# SC8701_EVM_RE1_0620.net
KiCad netlist of a schematic drawn in Altium Designer
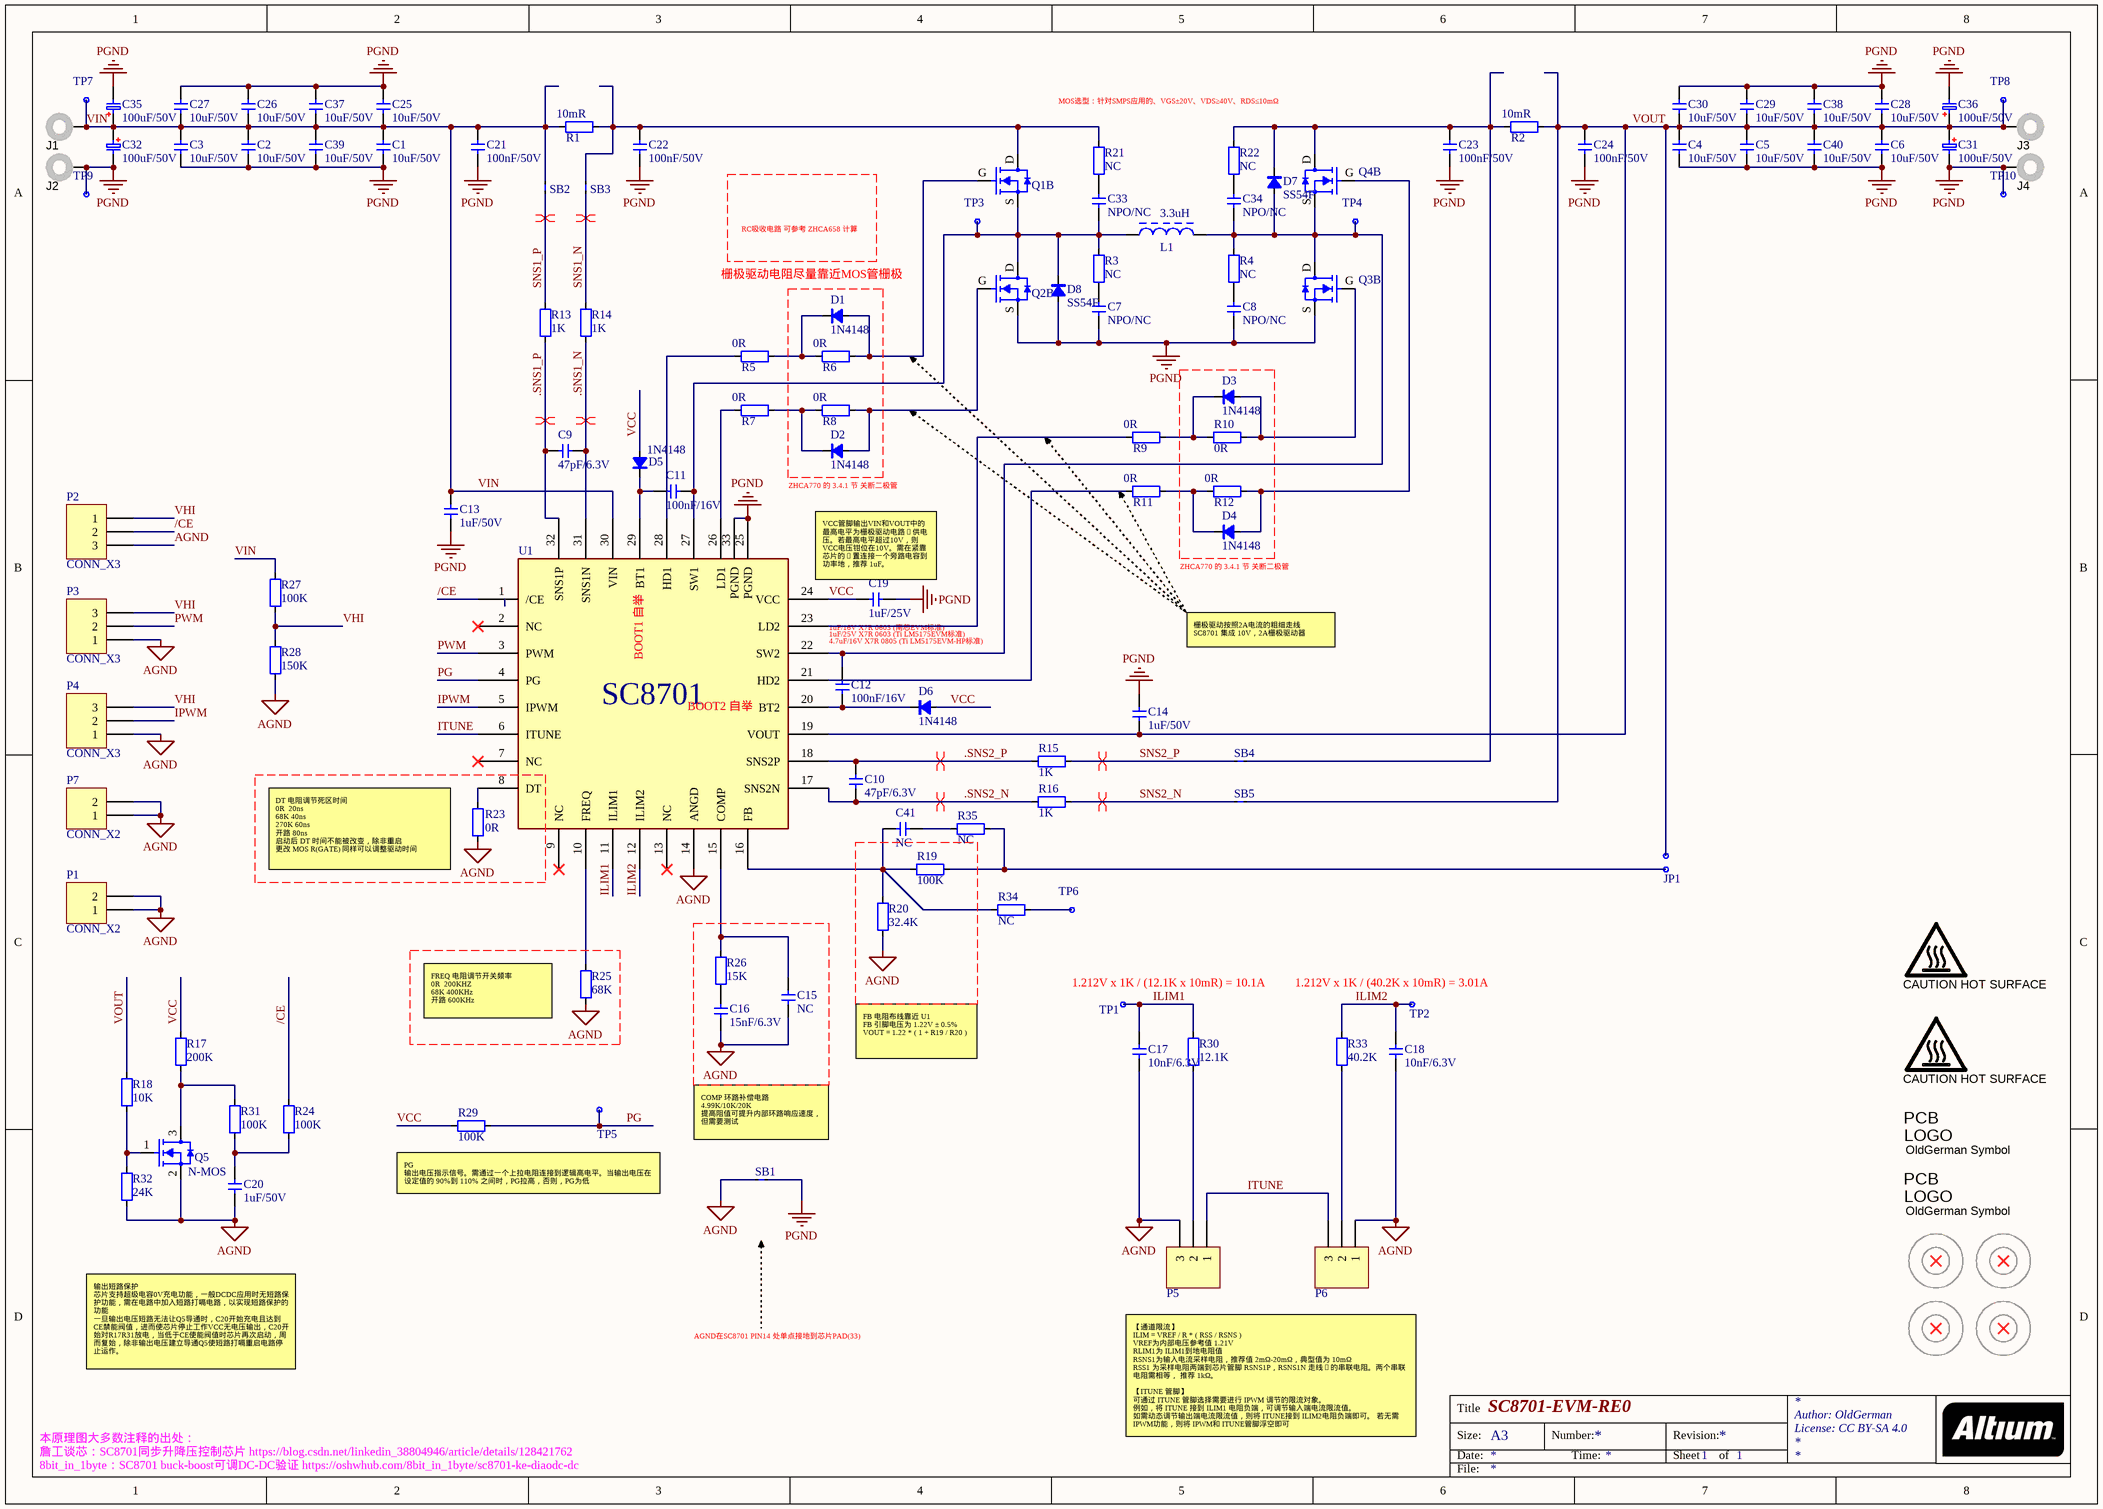
[diagram p0: SC8701_EVM_RE1_0620.SchDoc]

(export (version "E")
  (design (tool "Eeschema 10.0.6"))
  (components
    (comp (ref "C1")
      (value "10uF/50V")
      (footprint "C1210")
      (description "Capacitor")
      (libsource (lib "ODG_AD_Lib") (part "CAP"))
    )
    (comp (ref "C2")
      (value "10uF/50V")
      (footprint "C1210")
      (description "Capacitor")
      (libsource (lib "ODG_AD_Lib") (part "CAP"))
    )
    (comp (ref "C3")
      (value "10uF/50V")
      (footprint "C1210")
      (description "Capacitor")
      (libsource (lib "ODG_AD_Lib") (part "CAP"))
    )
    (comp (ref "C4")
      (value "10uF/50V")
      (footprint "C1210")
      (description "Capacitor")
      (libsource (lib "ODG_AD_Lib") (part "CAP"))
    )
    (comp (ref "C5")
      (value "10uF/50V")
      (footprint "C1210")
      (description "Capacitor")
      (libsource (lib "ODG_AD_Lib") (part "CAP"))
    )
    (comp (ref "C6")
      (value "10uF/50V")
      (footprint "C1210")
      (description "Capacitor")
      (libsource (lib "ODG_AD_Lib") (part "CAP"))
    )
    (comp (ref "C7")
      (value "NPO/NC")
      (footprint "C0805")
      (description "Capacitor")
      (libsource (lib "ODG_AD_Lib") (part "CAP"))
    )
    (comp (ref "C8")
      (value "NPO/NC")
      (footprint "C0805")
      (description "Capacitor")
      (libsource (lib "ODG_AD_Lib") (part "CAP"))
    )
    (comp (ref "C9")
      (value "47pF/6.3V")
      (footprint "C0603")
      (description "Capacitor")
      (libsource (lib "ODG_AD_Lib") (part "CAP"))
    )
    (comp (ref "C10")
      (value "47pF/6.3V")
      (footprint "C0603")
      (description "Capacitor")
      (libsource (lib "ODG_AD_Lib") (part "CAP"))
    )
    (comp (ref "C11")
      (value "100nF/16V")
      (footprint "C0603")
      (description "Capacitor")
      (libsource (lib "ODG_AD_Lib") (part "CAP"))
    )
    (comp (ref "C12")
      (value "100nF/16V")
      (footprint "C0603")
      (description "Capacitor")
      (libsource (lib "ODG_AD_Lib") (part "CAP"))
    )
    (comp (ref "C13")
      (value "1uF/50V")
      (footprint "C0603")
      (description "Capacitor")
      (libsource (lib "ODG_AD_Lib") (part "CAP"))
    )
    (comp (ref "C14")
      (value "1uF/50V")
      (footprint "C0603")
      (description "Capacitor")
      (libsource (lib "ODG_AD_Lib") (part "CAP"))
    )
    (comp (ref "C15")
      (value "NC")
      (footprint "C0603")
      (description "Capacitor")
      (libsource (lib "ODG_AD_Lib") (part "CAP"))
    )
    (comp (ref "C16")
      (value "15nF/6.3V")
      (footprint "C0603")
      (description "Capacitor")
      (libsource (lib "ODG_AD_Lib") (part "CAP"))
    )
    (comp (ref "C17")
      (value "10nF/6.3V")
      (footprint "C0603")
      (description "Capacitor")
      (libsource (lib "ODG_AD_Lib") (part "CAP"))
    )
    (comp (ref "C18")
      (value "10nF/6.3V")
      (footprint "C0603")
      (description "Capacitor")
      (libsource (lib "ODG_AD_Lib") (part "CAP"))
    )
    (comp (ref "C19")
      (value "1uF/25V")
      (footprint "C0805")
      (description "Capacitor")
      (libsource (lib "ODG_AD_Lib") (part "CAP"))
    )
    (comp (ref "C20")
      (value "1uF/50V")
      (footprint "C0603")
      (description "Capacitor")
      (libsource (lib "ODG_AD_Lib") (part "CAP"))
    )
    (comp (ref "C21")
      (value "100nF/50V")
      (footprint "C0603")
      (description "Capacitor")
      (libsource (lib "ODG_AD_Lib") (part "CAP"))
    )
    (comp (ref "C22")
      (value "100nF/50V")
      (footprint "C0603")
      (description "Capacitor")
      (libsource (lib "ODG_AD_Lib") (part "CAP"))
    )
    (comp (ref "C23")
      (value "100nF/50V")
      (footprint "C0603")
      (description "Capacitor")
      (libsource (lib "ODG_AD_Lib") (part "CAP"))
    )
    (comp (ref "C24")
      (value "100nF/50V")
      (footprint "C0603")
      (description "Capacitor")
      (libsource (lib "ODG_AD_Lib") (part "CAP"))
    )
    (comp (ref "C25")
      (value "10uF/50V")
      (footprint "C1210")
      (description "Capacitor")
      (libsource (lib "ODG_AD_Lib") (part "CAP"))
    )
    (comp (ref "C26")
      (value "10uF/50V")
      (footprint "C1210")
      (description "Capacitor")
      (libsource (lib "ODG_AD_Lib") (part "CAP"))
    )
    (comp (ref "C27")
      (value "10uF/50V")
      (footprint "C1210")
      (description "Capacitor")
      (libsource (lib "ODG_AD_Lib") (part "CAP"))
    )
    (comp (ref "C28")
      (value "10uF/50V")
      (footprint "C1210")
      (description "Capacitor")
      (libsource (lib "ODG_AD_Lib") (part "CAP"))
    )
    (comp (ref "C29")
      (value "10uF/50V")
      (footprint "C1210")
      (description "Capacitor")
      (libsource (lib "ODG_AD_Lib") (part "CAP"))
    )
    (comp (ref "C30")
      (value "10uF/50V")
      (footprint "C1210")
      (description "Capacitor")
      (libsource (lib "ODG_AD_Lib") (part "CAP"))
    )
    (comp (ref "C31")
      (value "100uF/50V")
      (footprint "CAP OS-CON D=10.0 L=10.0 F10")
      (description "Capacitor")
      (libsource (lib "ODG_AD_Lib") (part "CAP_Polar_Aluminum"))
    )
    (comp (ref "C32")
      (value "100uF/50V")
      (footprint "CAP OS-CON D=10.0 L=10.0 F10")
      (description "Capacitor")
      (libsource (lib "ODG_AD_Lib") (part "CAP_Polar_Aluminum"))
    )
    (comp (ref "C33")
      (value "NPO/NC")
      (footprint "C0805")
      (description "Capacitor")
      (libsource (lib "ODG_AD_Lib") (part "CAP"))
    )
    (comp (ref "C34")
      (value "NPO/NC")
      (footprint "C0805")
      (description "Capacitor")
      (libsource (lib "ODG_AD_Lib") (part "CAP"))
    )
    (comp (ref "C35")
      (value "100uF/50V")
      (footprint "CAP OS-CON D=10.0 L=10.0 F10")
      (description "Capacitor")
      (libsource (lib "ODG_AD_Lib") (part "CAP_Polar_Aluminum"))
    )
    (comp (ref "C36")
      (value "100uF/50V")
      (footprint "CAP OS-CON D=10.0 L=10.0 F10")
      (description "Capacitor")
      (libsource (lib "ODG_AD_Lib") (part "CAP_Polar_Aluminum"))
    )
    (comp (ref "C37")
      (value "10uF/50V")
      (footprint "C1210")
      (description "Capacitor")
      (libsource (lib "ODG_AD_Lib") (part "CAP"))
    )
    (comp (ref "C38")
      (value "10uF/50V")
      (footprint "C1210")
      (description "Capacitor")
      (libsource (lib "ODG_AD_Lib") (part "CAP"))
    )
    (comp (ref "C39")
      (value "10uF/50V")
      (footprint "C1210")
      (description "Capacitor")
      (libsource (lib "ODG_AD_Lib") (part "CAP"))
    )
    (comp (ref "C40")
      (value "10uF/50V")
      (footprint "C1210")
      (description "Capacitor")
      (libsource (lib "ODG_AD_Lib") (part "CAP"))
    )
    (comp (ref "C41")
      (value "NC")
      (footprint "C0603")
      (description "Capacitor")
      (libsource (lib "ODG_AD_Lib") (part "CAP"))
    )
    (comp (ref "D1")
      (value "1N4148")
      (footprint "SOD-323")
      (description "二极管")
      (libsource (lib "ODG_AD_Lib") (part "DIODE"))
    )
    (comp (ref "D2")
      (value "1N4148")
      (footprint "SOD-323")
      (description "二极管")
      (libsource (lib "ODG_AD_Lib") (part "DIODE"))
    )
    (comp (ref "D3")
      (value "1N4148")
      (footprint "SOD-323")
      (description "二极管")
      (libsource (lib "ODG_AD_Lib") (part "DIODE"))
    )
    (comp (ref "D4")
      (value "1N4148")
      (footprint "SOD-323")
      (description "二极管")
      (libsource (lib "ODG_AD_Lib") (part "DIODE"))
    )
    (comp (ref "D5")
      (value "1N4148")
      (footprint "SOD-323")
      (description "二极管")
      (libsource (lib "") (part "DIODE_2"))
    )
    (comp (ref "D6")
      (value "1N4148")
      (footprint "SOD-323")
      (description "二极管")
      (libsource (lib "ODG_AD_Lib") (part "DIODE"))
    )
    (comp (ref "D7")
      (value "SS54F")
      (footprint "SMAF")
      (description "二极管")
      (libsource (lib "") (part "DIODE_1"))
    )
    (comp (ref "D8")
      (value "SS54F")
      (footprint "SMAF")
      (description "二极管")
      (libsource (lib "") (part "DIODE_1"))
    )
    (comp (ref "H1") (value "HOLE") (footprint "M3.2 D=8") (libsource (lib "ODG_AD_Lib") (part "HOLE")))
    (comp (ref "H2") (value "HOLE") (footprint "M3.2 D=8") (libsource (lib "ODG_AD_Lib") (part "HOLE")))
    (comp (ref "H3") (value "HOLE") (footprint "M3.2 D=8") (libsource (lib "ODG_AD_Lib") (part "HOLE")))
    (comp (ref "H4") (value "HOLE") (footprint "M3.2 D=8") (libsource (lib "ODG_AD_Lib") (part "HOLE")))
    (comp (ref "J1")
      (value "U6047")
      (footprint "JACK_BANANA_U6047")
      (description "Banana Jack")
      (fields
        (field (name "PARTNUMBER") "575-8")
        (field (name "MANUFACTURER") "Keystone")
        (field (name "PUBLISHER") "Texas Instruments")
      )
      (libsource (lib "ODG_AD_Lib") (part "JACK_BANANA"))
    )
    (comp (ref "J2")
      (value "U6047")
      (footprint "JACK_BANANA_U6047")
      (description "Banana Jack")
      (fields
        (field (name "PARTNUMBER") "575-8")
        (field (name "MANUFACTURER") "Keystone")
        (field (name "PUBLISHER") "Texas Instruments")
      )
      (libsource (lib "ODG_AD_Lib") (part "JACK_BANANA"))
    )
    (comp (ref "J3")
      (value "U6047")
      (footprint "JACK_BANANA_U6047")
      (description "Banana Jack")
      (fields
        (field (name "PARTNUMBER") "575-8")
        (field (name "MANUFACTURER") "Keystone")
        (field (name "PUBLISHER") "Texas Instruments")
      )
      (libsource (lib "ODG_AD_Lib") (part "JACK_BANANA"))
    )
    (comp (ref "J4")
      (value "U6047")
      (footprint "JACK_BANANA_U6047")
      (description "Banana Jack")
      (fields
        (field (name "PARTNUMBER") "575-8")
        (field (name "MANUFACTURER") "Keystone")
        (field (name "PUBLISHER") "Texas Instruments")
      )
      (libsource (lib "ODG_AD_Lib") (part "JACK_BANANA"))
    )
    (comp (ref "JP1")
      (value "CONN_X2_DOT")
      (footprint "2.54mm_Male_x2")
      (libsource (lib "ODG_AD_Lib") (part "CONN_X2_DOT"))
    )
    (comp (ref "L1")
      (value "3.3uH")
      (footprint "INDUCTOR 1350 12.6X13.5X5.0mm")
      (description "135 功率电感 额定电流15A")
      (libsource (lib "ODG_AD_Lib") (part "Inductor_power"))
    )
    (comp (ref "LOGO1")
      (value "CAUTION HOT SURFACE")
      (footprint "IEC_HotSurface_Small")
      (description "IEC 61010-1 Hot Surface Warning")
      (fields (field (name "SYMBOLCREATOR") "a0412235") (field (name "PUBLISHER") "Texas Instruments"))
      (libsource (lib "ODG_AD_Lib") (part "IEC_HotSurface"))
    )
    (comp (ref "LOGO2")
      (value "CAUTION HOT SURFACE")
      (footprint "IEC_HotSurface_Small")
      (description "IEC 61010-1 Hot Surface Warning")
      (fields (field (name "SYMBOLCREATOR") "a0412235") (field (name "PUBLISHER") "Texas Instruments"))
      (libsource (lib "ODG_AD_Lib") (part "IEC_HotSurface"))
    )
    (comp (ref "Logo3")
      (value "OldGerman Symbol")
      (footprint "ODG_LOGO")
      (fields (field (name "SYMBOLCREATOR") "a0412235") (field (name "PUBLISHER") "Texas Instruments"))
      (libsource (lib "ODG_AD_Lib") (part "OldGeman"))
    )
    (comp (ref "Logo4")
      (value "OldGerman Symbol")
      (footprint "ODG_LOGO")
      (fields (field (name "SYMBOLCREATOR") "a0412235") (field (name "PUBLISHER") "Texas Instruments"))
      (libsource (lib "ODG_AD_Lib") (part "OldGeman"))
    )
    (comp (ref "P1")
      (value "CONN_X2")
      (footprint "2.54mm_Male_x2")
      (libsource (lib "ODG_AD_Lib") (part "CONN_X2"))
    )
    (comp (ref "P2") (value "CONN_X3") (footprint "2.54mm_Male_x3") (libsource (lib "") (part "CONN_X3_1")))
    (comp (ref "P3")
      (value "CONN_X3")
      (footprint "2.54mm_Male_x3")
      (libsource (lib "ODG_AD_Lib") (part "CONN_X3"))
    )
    (comp (ref "P4")
      (value "CONN_X3")
      (footprint "2.54mm_Male_x3")
      (libsource (lib "ODG_AD_Lib") (part "CONN_X3"))
    )
    (comp (ref "P5") (value "CONN_X3") (footprint "2.54mm_Male_x3") (libsource (lib "") (part "CONN_X3_1")))
    (comp (ref "P6") (value "CONN_X3") (footprint "2.54mm_Male_x3") (libsource (lib "") (part "CONN_X3_1")))
    (comp (ref "P7")
      (value "CONN_X2")
      (footprint "2.54mm_Male_x2")
      (libsource (lib "ODG_AD_Lib") (part "CONN_X2"))
    )
    (comp (ref "Q1B")
      (value "N-MOS_GDS")
      (footprint "SO8FL ROUND")
      (libsource (lib "ODG_AD_Lib") (part "N-MOS_GDS"))
    )
    (comp (ref "Q2B")
      (value "N-MOS_GDS")
      (footprint "SO8FL ROUND")
      (libsource (lib "ODG_AD_Lib") (part "N-MOS_GDS"))
    )
    (comp (ref "Q3B")
      (value "N-MOS_GDS")
      (footprint "SO8FL ROUND")
      (libsource (lib "ODG_AD_Lib") (part "N-MOS_GDS"))
    )
    (comp (ref "Q4B")
      (value "N-MOS_GDS")
      (footprint "SO8FL ROUND")
      (libsource (lib "ODG_AD_Lib") (part "N-MOS_GDS"))
    )
    (comp (ref "Q5")
      (value "N-MOS")
      (footprint "INFINEON SOT-23-3")
      (libsource (lib "ODG_AD_Lib") (part "N-MOS_123"))
    )
    (comp (ref "R1")
      (value "10mR")
      (footprint "R1206")
      (description "IEC Standard")
      (libsource (lib "") (part "RES_2"))
    )
    (comp (ref "R2")
      (value "10mR")
      (footprint "R1206")
      (description "IEC Standard")
      (libsource (lib "") (part "RES_2"))
    )
    (comp (ref "R3")
      (value "NC")
      (footprint "R0805")
      (description "IEC Standard")
      (libsource (lib "ODG_AD_Lib") (part "RES"))
    )
    (comp (ref "R4")
      (value "NC")
      (footprint "R0805")
      (description "IEC Standard")
      (libsource (lib "ODG_AD_Lib") (part "RES"))
    )
    (comp (ref "R5")
      (value "0R")
      (footprint "R0603")
      (description "IEC Standard")
      (libsource (lib "") (part "RES_2"))
    )
    (comp (ref "R6")
      (value "0R")
      (footprint "R0603")
      (description "IEC Standard")
      (libsource (lib "") (part "RES_2"))
    )
    (comp (ref "R7")
      (value "0R")
      (footprint "R0603")
      (description "IEC Standard")
      (libsource (lib "") (part "RES_2"))
    )
    (comp (ref "R8")
      (value "0R")
      (footprint "R0603")
      (description "IEC Standard")
      (libsource (lib "") (part "RES_2"))
    )
    (comp (ref "R9")
      (value "0R")
      (footprint "R0603")
      (description "IEC Standard")
      (libsource (lib "") (part "RES_2"))
    )
    (comp (ref "R10")
      (value "0R")
      (footprint "R0603")
      (description "IEC Standard")
      (libsource (lib "") (part "RES_2"))
    )
    (comp (ref "R11")
      (value "0R")
      (footprint "R0603")
      (description "IEC Standard")
      (libsource (lib "") (part "RES_2"))
    )
    (comp (ref "R12")
      (value "0R")
      (footprint "R0603")
      (description "IEC Standard")
      (libsource (lib "") (part "RES_2"))
    )
    (comp (ref "R13")
      (value "1K")
      (footprint "R0603")
      (description "IEC Standard")
      (libsource (lib "ODG_AD_Lib") (part "RES"))
    )
    (comp (ref "R14")
      (value "1K")
      (footprint "R0603")
      (description "IEC Standard")
      (libsource (lib "ODG_AD_Lib") (part "RES"))
    )
    (comp (ref "R15")
      (value "1K")
      (footprint "R0603")
      (description "IEC Standard")
      (libsource (lib "") (part "RES_1"))
    )
    (comp (ref "R16")
      (value "1K")
      (footprint "R0603")
      (description "IEC Standard")
      (libsource (lib "") (part "RES_1"))
    )
    (comp (ref "R17")
      (value "200K")
      (footprint "R0603")
      (description "IEC Standard")
      (libsource (lib "ODG_AD_Lib") (part "RES"))
    )
    (comp (ref "R18")
      (value "10K")
      (footprint "R0603")
      (description "IEC Standard")
      (libsource (lib "ODG_AD_Lib") (part "RES"))
    )
    (comp (ref "R19")
      (value "100K")
      (footprint "R0603")
      (description "IEC Standard")
      (libsource (lib "") (part "RES_2"))
    )
    (comp (ref "R20")
      (value "32.4K")
      (footprint "R0603")
      (description "IEC Standard")
      (libsource (lib "ODG_AD_Lib") (part "RES"))
    )
    (comp (ref "R21")
      (value "NC")
      (footprint "R0805")
      (description "IEC Standard")
      (libsource (lib "ODG_AD_Lib") (part "RES"))
    )
    (comp (ref "R22")
      (value "NC")
      (footprint "R0805")
      (description "IEC Standard")
      (libsource (lib "ODG_AD_Lib") (part "RES"))
    )
    (comp (ref "R23")
      (value "0R")
      (footprint "R0603")
      (description "IEC Standard")
      (libsource (lib "ODG_AD_Lib") (part "RES"))
    )
    (comp (ref "R24")
      (value "100K")
      (footprint "R0603")
      (description "IEC Standard")
      (libsource (lib "ODG_AD_Lib") (part "RES"))
    )
    (comp (ref "R25")
      (value "68K")
      (footprint "R0603")
      (description "IEC Standard")
      (libsource (lib "ODG_AD_Lib") (part "RES"))
    )
    (comp (ref "R26")
      (value "15K")
      (footprint "R0603")
      (description "IEC Standard")
      (libsource (lib "ODG_AD_Lib") (part "RES"))
    )
    (comp (ref "R27")
      (value "100K")
      (footprint "R0603")
      (description "IEC Standard")
      (libsource (lib "ODG_AD_Lib") (part "RES"))
    )
    (comp (ref "R28")
      (value "150K")
      (footprint "R0603")
      (description "IEC Standard")
      (libsource (lib "ODG_AD_Lib") (part "RES"))
    )
    (comp (ref "R29")
      (value "100K")
      (footprint "R0603")
      (description "IEC Standard")
      (libsource (lib "") (part "RES_2"))
    )
    (comp (ref "R30")
      (value "12.1K")
      (footprint "R0603")
      (description "IEC Standard")
      (libsource (lib "ODG_AD_Lib") (part "RES"))
    )
    (comp (ref "R31")
      (value "100K")
      (footprint "R0603")
      (description "IEC Standard")
      (libsource (lib "ODG_AD_Lib") (part "RES"))
    )
    (comp (ref "R32")
      (value "24K")
      (footprint "R0603")
      (description "IEC Standard")
      (libsource (lib "ODG_AD_Lib") (part "RES"))
    )
    (comp (ref "R33")
      (value "40.2K")
      (footprint "R0603")
      (description "IEC Standard")
      (libsource (lib "ODG_AD_Lib") (part "RES"))
    )
    (comp (ref "R34")
      (value "NC")
      (footprint "R0603")
      (description "IEC Standard")
      (libsource (lib "") (part "RES_1"))
    )
    (comp (ref "R35")
      (value "NC")
      (footprint "R0603")
      (description "IEC Standard")
      (libsource (lib "") (part "RES_1"))
    )
    (comp (ref "SB1")
      (value "NetTie_200um")
      (footprint "NetTie_200um")
      (description "Net Tie")
      (fields (field (name "PART NUMBER") "NetTie 0.2mm") (field (name "PUBLISHER") "Nordic Semiconductor"))
      (libsource (lib "pca63100") (part "NetTie 0.2mm"))
    )
    (comp (ref "SB2")
      (value "NetTie_200um")
      (footprint "NetTie_200um")
      (description "Net Tie")
      (fields (field (name "PART NUMBER") "NetTie 0.2mm") (field (name "PUBLISHER") "Nordic Semiconductor"))
      (libsource (lib "pca63100") (part "NetTie 0.2mm"))
    )
    (comp (ref "SB3")
      (value "NetTie_200um")
      (footprint "NetTie_200um")
      (description "Net Tie")
      (fields (field (name "PART NUMBER") "NetTie 0.2mm") (field (name "PUBLISHER") "Nordic Semiconductor"))
      (libsource (lib "pca63100") (part "NetTie 0.2mm"))
    )
    (comp (ref "SB4")
      (value "NetTie_200um")
      (footprint "NetTie_200um")
      (description "Net Tie")
      (fields (field (name "PART NUMBER") "NetTie 0.2mm") (field (name "PUBLISHER") "Nordic Semiconductor"))
      (libsource (lib "pca63100") (part "NetTie 0.2mm"))
    )
    (comp (ref "SB5")
      (value "NetTie_200um")
      (footprint "NetTie_200um")
      (description "Net Tie")
      (fields (field (name "PART NUMBER") "NetTie 0.2mm") (field (name "PUBLISHER") "Nordic Semiconductor"))
      (libsource (lib "pca63100") (part "NetTie 0.2mm"))
    )
    (comp (ref "TP1")
      (value "CONN_X1_DOT")
      (footprint "2.54mm_Male_x1")
      (libsource (lib "ODG_AD_Lib") (part "CONN_X1_DOT"))
    )
    (comp (ref "TP2")
      (value "CONN_X1_DOT")
      (footprint "2.54mm_Male_x1")
      (libsource (lib "ODG_AD_Lib") (part "CONN_X1_DOT"))
    )
    (comp (ref "TP3")
      (value "CONN_X1_DOT")
      (footprint "2.54mm_Male_x1")
      (libsource (lib "ODG_AD_Lib") (part "CONN_X1_DOT"))
    )
    (comp (ref "TP4")
      (value "CONN_X1_DOT")
      (footprint "2.54mm_Male_x1")
      (libsource (lib "ODG_AD_Lib") (part "CONN_X1_DOT"))
    )
    (comp (ref "TP5")
      (value "CONN_X1_DOT")
      (footprint "2.54mm_Male_x1")
      (libsource (lib "ODG_AD_Lib") (part "CONN_X1_DOT"))
    )
    (comp (ref "TP6")
      (value "CONN_X1_DOT")
      (footprint "2.54mm_Male_x1")
      (libsource (lib "ODG_AD_Lib") (part "CONN_X1_DOT"))
    )
    (comp (ref "TP7")
      (value "CONN_X1_DOT")
      (footprint "2.54mm_Male_x1")
      (libsource (lib "ODG_AD_Lib") (part "CONN_X1_DOT"))
    )
    (comp (ref "TP8")
      (value "CONN_X1_DOT")
      (footprint "2.54mm_Male_x1")
      (libsource (lib "ODG_AD_Lib") (part "CONN_X1_DOT"))
    )
    (comp (ref "TP9")
      (value "CONN_X1_DOT")
      (footprint "2.54mm_Male_x1")
      (libsource (lib "ODG_AD_Lib") (part "CONN_X1_DOT"))
    )
    (comp (ref "TP10")
      (value "CONN_X1_DOT")
      (footprint "2.54mm_Male_x1")
      (libsource (lib "ODG_AD_Lib") (part "CONN_X1_DOT"))
    )
    (comp (ref "U1")
      (value "SC8701 (A)")
      (footprint "TQFN-32 4X4MM 0.4 VIA")
      (description "高效率, 同步, 4 管升降压控制器")
      (libsource (lib "ODG_AD_Lib") (part "SC8701 (A)"))
    )
  )
  (nets
    (net (code "1") (name "/.SNS1_N") (class "Default")
      (node (ref "C9") (pin "2") (pinfunction "2_2") (pintype "passive"))
      (node (ref "R14") (pin "1") (pinfunction "1_1") (pintype "passive"))
      (node (ref "U1") (pin "31") (pinfunction "SNS1N_31") (pintype "passive"))
    )
    (net (code "2") (name "/.SNS1_P") (class "Default")
      (node (ref "C9") (pin "1") (pinfunction "1_1") (pintype "passive"))
      (node (ref "R13") (pin "1") (pinfunction "1_1") (pintype "passive"))
      (node (ref "U1") (pin "32") (pinfunction "SNS1P_32") (pintype "passive"))
    )
    (net (code "3") (name "/.SNS2_N") (class "Default")
      (node (ref "C10") (pin "2") (pinfunction "2_2") (pintype "passive"))
      (node (ref "R16") (pin "2") (pinfunction "2_2") (pintype "passive"))
      (node (ref "U1") (pin "17") (pinfunction "SNS2N_17") (pintype "passive"))
    )
    (net (code "4") (name "/.SNS2_P") (class "Default")
      (node (ref "C10") (pin "1") (pinfunction "1_1") (pintype "passive"))
      (node (ref "R15") (pin "2") (pinfunction "2_2") (pintype "passive"))
      (node (ref "U1") (pin "18") (pinfunction "SNS2P_18") (pintype "passive"))
    )
    (net (code "5") (name "/ILIM1") (class "Default")
      (node (ref "C17") (pin "2") (pinfunction "2_2") (pintype "passive"))
      (node (ref "R30") (pin "2") (pinfunction "2_2") (pintype "passive"))
      (node (ref "TP1") (pin "1") (pinfunction "1_1") (pintype "passive"))
      (node (ref "U1") (pin "11") (pinfunction "ILIM1_11") (pintype "passive"))
    )
    (net (code "6") (name "/ILIM2") (class "Default")
      (node (ref "C18") (pin "2") (pinfunction "2_2") (pintype "passive"))
      (node (ref "R33") (pin "2") (pinfunction "2_2") (pintype "passive"))
      (node (ref "TP2") (pin "1") (pinfunction "1_1") (pintype "passive"))
      (node (ref "U1") (pin "12") (pinfunction "ILIM2_12") (pintype "passive"))
    )
    (net (code "7") (name "/IPWM") (class "Default")
      (node (ref "P4") (pin "2") (pinfunction "2_2") (pintype "passive"))
      (node (ref "U1") (pin "5") (pinfunction "IPWM_5") (pintype "passive"))
    )
    (net (code "8") (name "/ITUNE") (class "Default")
      (node (ref "P5") (pin "1") (pinfunction "1_1") (pintype "passive"))
      (node (ref "P6") (pin "3") (pinfunction "3_3") (pintype "passive"))
      (node (ref "U1") (pin "6") (pinfunction "ITUNE_6") (pintype "passive"))
    )
    (net (code "9") (name "/PG") (class "Default")
      (node (ref "R29") (pin "2") (pinfunction "2_2") (pintype "passive"))
      (node (ref "TP5") (pin "1") (pinfunction "1_1") (pintype "passive"))
      (node (ref "U1") (pin "4") (pinfunction "PG_4") (pintype "passive"))
    )
    (net (code "10") (name "/PWM") (class "Default")
      (node (ref "P3") (pin "2") (pinfunction "2_2") (pintype "passive"))
      (node (ref "U1") (pin "3") (pinfunction "PWM_3") (pintype "passive"))
    )
    (net (code "11") (name "/SNS1_N") (class "Default")
      (node (ref "R14") (pin "2") (pinfunction "2_2") (pintype "passive"))
      (node (ref "SB3") (pin "1") (pinfunction "1_1") (pintype "passive"))
    )
    (net (code "12") (name "/SNS1_P") (class "Default")
      (node (ref "R13") (pin "2") (pinfunction "2_2") (pintype "passive"))
      (node (ref "SB2") (pin "1") (pinfunction "1_1") (pintype "passive"))
    )
    (net (code "13") (name "/SNS2_N") (class "Default")
      (node (ref "R16") (pin "1") (pinfunction "1_1") (pintype "passive"))
      (node (ref "SB5") (pin "1") (pinfunction "1_1") (pintype "passive"))
    )
    (net (code "14") (name "/SNS2_P") (class "Default")
      (node (ref "R15") (pin "1") (pinfunction "1_1") (pintype "passive"))
      (node (ref "SB4") (pin "1") (pinfunction "1_1") (pintype "passive"))
    )
    (net (code "15") (name "/VCC") (class "Default")
      (node (ref "C19") (pin "1") (pinfunction "1_1") (pintype "passive"))
      (node (ref "D5") (pin "1") (pinfunction "A_1") (pintype "passive"))
      (node (ref "D6") (pin "1") (pinfunction "A_1") (pintype "passive"))
      (node (ref "R17") (pin "2") (pinfunction "2_2") (pintype "passive"))
      (node (ref "R29") (pin "1") (pinfunction "1_1") (pintype "passive"))
      (node (ref "U1") (pin "24") (pinfunction "VCC_24") (pintype "passive"))
    )
    (net (code "16") (name "/VHI") (class "Default")
      (node (ref "P2") (pin "1") (pinfunction "1_1") (pintype "passive"))
      (node (ref "P3") (pin "3") (pinfunction "3_3") (pintype "passive"))
      (node (ref "P4") (pin "3") (pinfunction "3_3") (pintype "passive"))
      (node (ref "R27") (pin "1") (pinfunction "1_1") (pintype "passive"))
      (node (ref "R28") (pin "2") (pinfunction "2_2") (pintype "passive"))
    )
    (net (code "17") (name "/VIN") (class "Default")
      (node (ref "C1") (pin "2") (pinfunction "2_2") (pintype "passive"))
      (node (ref "C13") (pin "1") (pinfunction "1_1") (pintype "passive"))
      (node (ref "C2") (pin "2") (pinfunction "2_2") (pintype "passive"))
      (node (ref "C21") (pin "2") (pinfunction "2_2") (pintype "passive"))
      (node (ref "C25") (pin "2") (pinfunction "2_2") (pintype "passive"))
      (node (ref "C26") (pin "2") (pinfunction "2_2") (pintype "passive"))
      (node (ref "C27") (pin "2") (pinfunction "2_2") (pintype "passive"))
      (node (ref "C3") (pin "2") (pinfunction "2_2") (pintype "passive"))
      (node (ref "C32") (pin "1") (pinfunction "1_1") (pintype "passive"))
      (node (ref "C35") (pin "1") (pinfunction "1_1") (pintype "passive"))
      (node (ref "C37") (pin "2") (pinfunction "2_2") (pintype "passive"))
      (node (ref "C39") (pin "2") (pinfunction "2_2") (pintype "passive"))
      (node (ref "J1") (pin "1") (pinfunction "1_1") (pintype "passive"))
      (node (ref "R1") (pin "1") (pinfunction "1_1") (pintype "passive"))
      (node (ref "R27") (pin "2") (pinfunction "2_2") (pintype "passive"))
      (node (ref "SB2") (pin "2") (pinfunction "2_2") (pintype "passive"))
      (node (ref "TP7") (pin "1") (pinfunction "1_1") (pintype "passive"))
      (node (ref "U1") (pin "30") (pinfunction "VIN_30") (pintype "passive"))
    )
    (net (code "18") (name "/VOUT") (class "Default")
      (node (ref "C14") (pin "1") (pinfunction "1_1") (pintype "passive"))
      (node (ref "C24") (pin "2") (pinfunction "2_2") (pintype "passive"))
      (node (ref "C28") (pin "2") (pinfunction "2_2") (pintype "passive"))
      (node (ref "C29") (pin "2") (pinfunction "2_2") (pintype "passive"))
      (node (ref "C30") (pin "2") (pinfunction "2_2") (pintype "passive"))
      (node (ref "C31") (pin "1") (pinfunction "1_1") (pintype "passive"))
      (node (ref "C36") (pin "1") (pinfunction "1_1") (pintype "passive"))
      (node (ref "C38") (pin "2") (pinfunction "2_2") (pintype "passive"))
      (node (ref "C4") (pin "2") (pinfunction "2_2") (pintype "passive"))
      (node (ref "C40") (pin "2") (pinfunction "2_2") (pintype "passive"))
      (node (ref "C5") (pin "2") (pinfunction "2_2") (pintype "passive"))
      (node (ref "C6") (pin "2") (pinfunction "2_2") (pintype "passive"))
      (node (ref "J3") (pin "1") (pinfunction "1_1") (pintype "passive"))
      (node (ref "JP1") (pin "1") (pinfunction "1_1") (pintype "passive"))
      (node (ref "R18") (pin "2") (pinfunction "2_2") (pintype "passive"))
      (node (ref "R2") (pin "2") (pinfunction "2_2") (pintype "passive"))
      (node (ref "SB5") (pin "2") (pinfunction "2_2") (pintype "passive"))
      (node (ref "TP8") (pin "1") (pinfunction "1_1") (pintype "passive"))
      (node (ref "U1") (pin "19") (pinfunction "VOUT_19") (pintype "passive"))
    )
    (net (code "19") (name "/{slash}CE") (class "Default")
      (node (ref "P2") (pin "2") (pinfunction "2_2") (pintype "passive"))
      (node (ref "R24") (pin "2") (pinfunction "2_2") (pintype "passive"))
      (node (ref "U1") (pin "1") (pinfunction "/CE_1") (pintype "passive"))
    )
    (net (code "20") (name "AGND") (class "Default")
      (node (ref "C15") (pin "1") (pinfunction "1_1") (pintype "passive"))
      (node (ref "C16") (pin "1") (pinfunction "1_1") (pintype "passive"))
      (node (ref "C17") (pin "1") (pinfunction "1_1") (pintype "passive"))
      (node (ref "C18") (pin "1") (pinfunction "1_1") (pintype "passive"))
      (node (ref "C20") (pin "2") (pinfunction "2_2") (pintype "passive"))
      (node (ref "P1") (pin "1") (pinfunction "1_1") (pintype "passive"))
      (node (ref "P1") (pin "2") (pinfunction "2_2") (pintype "passive"))
      (node (ref "P2") (pin "3") (pinfunction "3_3") (pintype "passive"))
      (node (ref "P3") (pin "1") (pinfunction "1_1") (pintype "passive"))
      (node (ref "P4") (pin "1") (pinfunction "1_1") (pintype "passive"))
      (node (ref "P5") (pin "3") (pinfunction "3_3") (pintype "passive"))
      (node (ref "P6") (pin "1") (pinfunction "1_1") (pintype "passive"))
      (node (ref "P7") (pin "1") (pinfunction "1_1") (pintype "passive"))
      (node (ref "P7") (pin "2") (pinfunction "2_2") (pintype "passive"))
      (node (ref "Q5") (pin "2") (pinfunction "S_2") (pintype "passive"))
      (node (ref "R20") (pin "1") (pinfunction "1_1") (pintype "passive"))
      (node (ref "R23") (pin "1") (pinfunction "1_1") (pintype "passive"))
      (node (ref "R25") (pin "1") (pinfunction "1_1") (pintype "passive"))
      (node (ref "R28") (pin "1") (pinfunction "1_1") (pintype "passive"))
      (node (ref "R32") (pin "1") (pinfunction "1_1") (pintype "passive"))
      (node (ref "SB1") (pin "1") (pinfunction "1_1") (pintype "passive"))
      (node (ref "U1") (pin "14") (pinfunction "ANGD_14") (pintype "passive"))
    )
    (net (code "21") (name "Net-(C7-Pad2)") (class "Default")
      (node (ref "C7") (pin "2") (pinfunction "2_2") (pintype "passive"))
      (node (ref "R3") (pin "1") (pinfunction "1_1") (pintype "passive"))
    )
    (net (code "22") (name "Net-(C8-Pad2)") (class "Default")
      (node (ref "C8") (pin "2") (pinfunction "2_2") (pintype "passive"))
      (node (ref "R4") (pin "1") (pinfunction "1_1") (pintype "passive"))
    )
    (net (code "23") (name "Net-(C16-Pad2)") (class "Default")
      (node (ref "C16") (pin "2") (pinfunction "2_2") (pintype "passive"))
      (node (ref "R26") (pin "1") (pinfunction "1_1") (pintype "passive"))
    )
    (net (code "24") (name "Net-(C20-Pad1)") (class "Default")
      (node (ref "C20") (pin "1") (pinfunction "1_1") (pintype "passive"))
      (node (ref "R24") (pin "1") (pinfunction "1_1") (pintype "passive"))
      (node (ref "R31") (pin "1") (pinfunction "1_1") (pintype "passive"))
    )
    (net (code "25") (name "Net-(C22-Pad2)") (class "Default")
      (node (ref "C22") (pin "2") (pinfunction "2_2") (pintype "passive"))
      (node (ref "Q1B") (pin "D") (pinfunction "D_D") (pintype "passive"))
      (node (ref "R1") (pin "2") (pinfunction "2_2") (pintype "passive"))
      (node (ref "R21") (pin "2") (pinfunction "2_2") (pintype "passive"))
      (node (ref "SB3") (pin "2") (pinfunction "2_2") (pintype "passive"))
    )
    (net (code "26") (name "Net-(C33-Pad2)") (class "Default")
      (node (ref "C33") (pin "2") (pinfunction "2_2") (pintype "passive"))
      (node (ref "R21") (pin "1") (pinfunction "1_1") (pintype "passive"))
    )
    (net (code "27") (name "Net-(C34-Pad2)") (class "Default")
      (node (ref "C34") (pin "2") (pinfunction "2_2") (pintype "passive"))
      (node (ref "R22") (pin "1") (pinfunction "1_1") (pintype "passive"))
    )
    (net (code "28") (name "Net-(C41-Pad2)") (class "Default")
      (node (ref "C41") (pin "2") (pinfunction "2_2") (pintype "passive"))
      (node (ref "R35") (pin "2") (pinfunction "2_2") (pintype "passive"))
    )
    (net (code "29") (name "Net-(D1-A)") (class "Default")
      (node (ref "D1") (pin "1") (pinfunction "A_1") (pintype "passive"))
      (node (ref "Q1B") (pin "G") (pinfunction "G_G") (pintype "passive"))
      (node (ref "R6") (pin "2") (pinfunction "2_2") (pintype "passive"))
    )
    (net (code "30") (name "Net-(D1-C)") (class "Default")
      (node (ref "D1") (pin "2") (pinfunction "C_2") (pintype "passive"))
      (node (ref "R5") (pin "2") (pinfunction "2_2") (pintype "passive"))
      (node (ref "R6") (pin "1") (pinfunction "1_1") (pintype "passive"))
    )
    (net (code "31") (name "Net-(D2-A)") (class "Default")
      (node (ref "D2") (pin "1") (pinfunction "A_1") (pintype "passive"))
      (node (ref "Q2B") (pin "G") (pinfunction "G_G") (pintype "passive"))
      (node (ref "R8") (pin "2") (pinfunction "2_2") (pintype "passive"))
    )
    (net (code "32") (name "Net-(D2-C)") (class "Default")
      (node (ref "D2") (pin "2") (pinfunction "C_2") (pintype "passive"))
      (node (ref "R7") (pin "2") (pinfunction "2_2") (pintype "passive"))
      (node (ref "R8") (pin "1") (pinfunction "1_1") (pintype "passive"))
    )
    (net (code "33") (name "Net-(D3-A)") (class "Default")
      (node (ref "D3") (pin "1") (pinfunction "A_1") (pintype "passive"))
      (node (ref "Q3B") (pin "G") (pinfunction "G_G") (pintype "passive"))
      (node (ref "R10") (pin "2") (pinfunction "2_2") (pintype "passive"))
    )
    (net (code "34") (name "Net-(D3-C)") (class "Default")
      (node (ref "D3") (pin "2") (pinfunction "C_2") (pintype "passive"))
      (node (ref "R10") (pin "1") (pinfunction "1_1") (pintype "passive"))
      (node (ref "R9") (pin "2") (pinfunction "2_2") (pintype "passive"))
    )
    (net (code "35") (name "Net-(D4-A)") (class "Default")
      (node (ref "D4") (pin "1") (pinfunction "A_1") (pintype "passive"))
      (node (ref "Q4B") (pin "G") (pinfunction "G_G") (pintype "passive"))
      (node (ref "R12") (pin "2") (pinfunction "2_2") (pintype "passive"))
    )
    (net (code "36") (name "Net-(D4-C)") (class "Default")
      (node (ref "D4") (pin "2") (pinfunction "C_2") (pintype "passive"))
      (node (ref "R11") (pin "2") (pinfunction "2_2") (pintype "passive"))
      (node (ref "R12") (pin "1") (pinfunction "1_1") (pintype "passive"))
    )
    (net (code "37") (name "Net-(D5-C)") (class "Default")
      (node (ref "C11") (pin "1") (pinfunction "1_1") (pintype "passive"))
      (node (ref "D5") (pin "2") (pinfunction "C_2") (pintype "passive"))
      (node (ref "U1") (pin "29") (pinfunction "BT1_29") (pintype "passive"))
    )
    (net (code "38") (name "Net-(D6-C)") (class "Default")
      (node (ref "C12") (pin "2") (pinfunction "2_2") (pintype "passive"))
      (node (ref "D6") (pin "2") (pinfunction "C_2") (pintype "passive"))
      (node (ref "U1") (pin "20") (pinfunction "BT2_20") (pintype "passive"))
    )
    (net (code "39") (name "Net-(D7-A)") (class "Default")
      (node (ref "C12") (pin "1") (pinfunction "1_1") (pintype "passive"))
      (node (ref "C34") (pin "1") (pinfunction "1_1") (pintype "passive"))
      (node (ref "D7") (pin "1") (pinfunction "A_1") (pintype "passive"))
      (node (ref "L1") (pin "2") (pinfunction "2_2") (pintype "passive"))
      (node (ref "Q3B") (pin "D") (pinfunction "D_D") (pintype "passive"))
      (node (ref "Q4B") (pin "S") (pinfunction "S_S") (pintype "passive"))
      (node (ref "R4") (pin "2") (pinfunction "2_2") (pintype "passive"))
      (node (ref "TP4") (pin "1") (pinfunction "1_1") (pintype "passive"))
      (node (ref "U1") (pin "22") (pinfunction "SW2_22") (pintype "passive"))
    )
    (net (code "40") (name "Net-(D7-C)") (class "Default")
      (node (ref "C23") (pin "2") (pinfunction "2_2") (pintype "passive"))
      (node (ref "D7") (pin "2") (pinfunction "C_2") (pintype "passive"))
      (node (ref "Q4B") (pin "D") (pinfunction "D_D") (pintype "passive"))
      (node (ref "R2") (pin "1") (pinfunction "1_1") (pintype "passive"))
      (node (ref "R22") (pin "2") (pinfunction "2_2") (pintype "passive"))
      (node (ref "SB4") (pin "2") (pinfunction "2_2") (pintype "passive"))
    )
    (net (code "41") (name "Net-(D8-C)") (class "Default")
      (node (ref "C11") (pin "2") (pinfunction "2_2") (pintype "passive"))
      (node (ref "C33") (pin "1") (pinfunction "1_1") (pintype "passive"))
      (node (ref "D8") (pin "2") (pinfunction "C_2") (pintype "passive"))
      (node (ref "L1") (pin "1") (pintype "passive"))
      (node (ref "Q1B") (pin "S") (pinfunction "S_S") (pintype "passive"))
      (node (ref "Q2B") (pin "D") (pinfunction "D_D") (pintype "passive"))
      (node (ref "R3") (pin "2") (pinfunction "2_2") (pintype "passive"))
      (node (ref "TP3") (pin "1") (pinfunction "1_1") (pintype "passive"))
      (node (ref "U1") (pin "27") (pinfunction "SW1_27") (pintype "passive"))
    )
    (net (code "42") (name "Net-(JP1-Pad2)") (class "Default")
      (node (ref "JP1") (pin "2") (pinfunction "2_2") (pintype "passive"))
      (node (ref "R19") (pin "2") (pinfunction "2_2") (pintype "passive"))
      (node (ref "R35") (pin "1") (pinfunction "1_1") (pintype "passive"))
    )
    (net (code "43") (name "Net-(P5-Pad2)") (class "Default")
      (node (ref "P5") (pin "2") (pinfunction "2_2") (pintype "passive"))
      (node (ref "R30") (pin "1") (pinfunction "1_1") (pintype "passive"))
    )
    (net (code "44") (name "Net-(P6-Pad2)") (class "Default")
      (node (ref "P6") (pin "2") (pinfunction "2_2") (pintype "passive"))
      (node (ref "R33") (pin "1") (pinfunction "1_1") (pintype "passive"))
    )
    (net (code "45") (name "Net-(Q5-D)") (class "Default")
      (node (ref "Q5") (pin "3") (pinfunction "D_3") (pintype "passive"))
      (node (ref "R17") (pin "1") (pinfunction "1_1") (pintype "passive"))
      (node (ref "R31") (pin "2") (pinfunction "2_2") (pintype "passive"))
    )
    (net (code "46") (name "Net-(Q5-G)") (class "Default")
      (node (ref "Q5") (pin "1") (pinfunction "G_1") (pintype "passive"))
      (node (ref "R18") (pin "1") (pinfunction "1_1") (pintype "passive"))
      (node (ref "R32") (pin "2") (pinfunction "2_2") (pintype "passive"))
    )
    (net (code "47") (name "Net-(R34-Pad1)") (class "Default")
      (node (ref "R34") (pin "1") (pinfunction "1_1") (pintype "passive"))
      (node (ref "TP6") (pin "1") (pinfunction "1_1") (pintype "passive"))
    )
    (net (code "48") (name "Net-(U1-COMP)") (class "Default")
      (node (ref "C15") (pin "2") (pinfunction "2_2") (pintype "passive"))
      (node (ref "R26") (pin "2") (pinfunction "2_2") (pintype "passive"))
      (node (ref "U1") (pin "15") (pinfunction "COMP_15") (pintype "passive"))
    )
    (net (code "49") (name "Net-(U1-DT)") (class "Default")
      (node (ref "R23") (pin "2") (pinfunction "2_2") (pintype "passive"))
      (node (ref "U1") (pin "8") (pinfunction "DT_8") (pintype "passive"))
    )
    (net (code "50") (name "Net-(U1-FB)") (class "Default")
      (node (ref "C41") (pin "1") (pinfunction "1_1") (pintype "passive"))
      (node (ref "R19") (pin "1") (pinfunction "1_1") (pintype "passive"))
      (node (ref "R20") (pin "2") (pinfunction "2_2") (pintype "passive"))
      (node (ref "R34") (pin "2") (pinfunction "2_2") (pintype "passive"))
      (node (ref "U1") (pin "16") (pinfunction "FB_16") (pintype "passive"))
    )
    (net (code "51") (name "Net-(U1-FREQ)") (class "Default")
      (node (ref "R25") (pin "2") (pinfunction "2_2") (pintype "passive"))
      (node (ref "U1") (pin "10") (pinfunction "FREQ_10") (pintype "passive"))
    )
    (net (code "52") (name "Net-(U1-HD1)") (class "Default")
      (node (ref "R5") (pin "1") (pinfunction "1_1") (pintype "passive"))
      (node (ref "U1") (pin "28") (pinfunction "HD1_28") (pintype "passive"))
    )
    (net (code "53") (name "Net-(U1-HD2)") (class "Default")
      (node (ref "R11") (pin "1") (pinfunction "1_1") (pintype "passive"))
      (node (ref "U1") (pin "21") (pinfunction "HD2_21") (pintype "passive"))
    )
    (net (code "54") (name "Net-(U1-LD1)") (class "Default")
      (node (ref "R7") (pin "1") (pinfunction "1_1") (pintype "passive"))
      (node (ref "U1") (pin "26") (pinfunction "LD1_26") (pintype "passive"))
    )
    (net (code "55") (name "Net-(U1-LD2)") (class "Default")
      (node (ref "R9") (pin "1") (pinfunction "1_1") (pintype "passive"))
      (node (ref "U1") (pin "23") (pinfunction "LD2_23") (pintype "passive"))
    )
    (net (code "56") (name "PGND") (class "Default")
      (node (ref "C1") (pin "1") (pinfunction "1_1") (pintype "passive"))
      (node (ref "C13") (pin "2") (pinfunction "2_2") (pintype "passive"))
      (node (ref "C14") (pin "2") (pinfunction "2_2") (pintype "passive"))
      (node (ref "C19") (pin "2") (pinfunction "2_2") (pintype "passive"))
      (node (ref "C2") (pin "1") (pinfunction "1_1") (pintype "passive"))
      (node (ref "C21") (pin "1") (pinfunction "1_1") (pintype "passive"))
      (node (ref "C22") (pin "1") (pinfunction "1_1") (pintype "passive"))
      (node (ref "C23") (pin "1") (pinfunction "1_1") (pintype "passive"))
      (node (ref "C24") (pin "1") (pinfunction "1_1") (pintype "passive"))
      (node (ref "C25") (pin "1") (pinfunction "1_1") (pintype "passive"))
      (node (ref "C26") (pin "1") (pinfunction "1_1") (pintype "passive"))
      (node (ref "C27") (pin "1") (pinfunction "1_1") (pintype "passive"))
      (node (ref "C28") (pin "1") (pinfunction "1_1") (pintype "passive"))
      (node (ref "C29") (pin "1") (pinfunction "1_1") (pintype "passive"))
      (node (ref "C3") (pin "1") (pinfunction "1_1") (pintype "passive"))
      (node (ref "C30") (pin "1") (pinfunction "1_1") (pintype "passive"))
      (node (ref "C31") (pin "2") (pinfunction "2_2") (pintype "passive"))
      (node (ref "C32") (pin "2") (pinfunction "2_2") (pintype "passive"))
      (node (ref "C35") (pin "2") (pinfunction "2_2") (pintype "passive"))
      (node (ref "C36") (pin "2") (pinfunction "2_2") (pintype "passive"))
      (node (ref "C37") (pin "1") (pinfunction "1_1") (pintype "passive"))
      (node (ref "C38") (pin "1") (pinfunction "1_1") (pintype "passive"))
      (node (ref "C39") (pin "1") (pinfunction "1_1") (pintype "passive"))
      (node (ref "C4") (pin "1") (pinfunction "1_1") (pintype "passive"))
      (node (ref "C40") (pin "1") (pinfunction "1_1") (pintype "passive"))
      (node (ref "C5") (pin "1") (pinfunction "1_1") (pintype "passive"))
      (node (ref "C6") (pin "1") (pinfunction "1_1") (pintype "passive"))
      (node (ref "C7") (pin "1") (pinfunction "1_1") (pintype "passive"))
      (node (ref "C8") (pin "1") (pinfunction "1_1") (pintype "passive"))
      (node (ref "D8") (pin "1") (pinfunction "A_1") (pintype "passive"))
      (node (ref "J2") (pin "1") (pinfunction "1_1") (pintype "passive"))
      (node (ref "J4") (pin "1") (pinfunction "1_1") (pintype "passive"))
      (node (ref "Q2B") (pin "S") (pinfunction "S_S") (pintype "passive"))
      (node (ref "Q3B") (pin "S") (pinfunction "S_S") (pintype "passive"))
      (node (ref "SB1") (pin "2") (pinfunction "2_2") (pintype "passive"))
      (node (ref "TP10") (pin "1") (pinfunction "1_1") (pintype "passive"))
      (node (ref "TP9") (pin "1") (pinfunction "1_1") (pintype "passive"))
      (node (ref "U1") (pin "25") (pinfunction "PGND_25") (pintype "passive"))
      (node (ref "U1") (pin "33") (pinfunction "PGND_33") (pintype "passive"))
    )
    (net (code "57") (name "unconnected-(H1-Pad1)") (class "Default")
      (node (ref "H1") (pin "1") (pinfunction "1_1") (pintype "passive+no_connect"))
    )
    (net (code "58") (name "unconnected-(H2-Pad1)") (class "Default")
      (node (ref "H2") (pin "1") (pinfunction "1_1") (pintype "passive+no_connect"))
    )
    (net (code "59") (name "unconnected-(H3-Pad1)") (class "Default")
      (node (ref "H3") (pin "1") (pinfunction "1_1") (pintype "passive+no_connect"))
    )
    (net (code "60") (name "unconnected-(H4-Pad1)") (class "Default")
      (node (ref "H4") (pin "1") (pinfunction "1_1") (pintype "passive+no_connect"))
    )
    (net (code "61") (name "unconnected-(U1-NC-Pad2)") (class "Default")
      (node (ref "U1") (pin "2") (pinfunction "NC_2") (pintype "passive+no_connect"))
    )
    (net (code "62") (name "unconnected-(U1-NC-Pad7)") (class "Default")
      (node (ref "U1") (pin "7") (pinfunction "NC_7") (pintype "passive+no_connect"))
    )
    (net (code "63") (name "unconnected-(U1-NC-Pad9)") (class "Default")
      (node (ref "U1") (pin "9") (pinfunction "NC_9") (pintype "passive+no_connect"))
    )
    (net (code "64") (name "unconnected-(U1-NC-Pad13)") (class "Default")
      (node (ref "U1") (pin "13") (pinfunction "NC_13") (pintype "passive+no_connect"))
    )
  )
)
